# Brduino-Main.net
KiCad netlist of a schematic drawn in Altium Designer
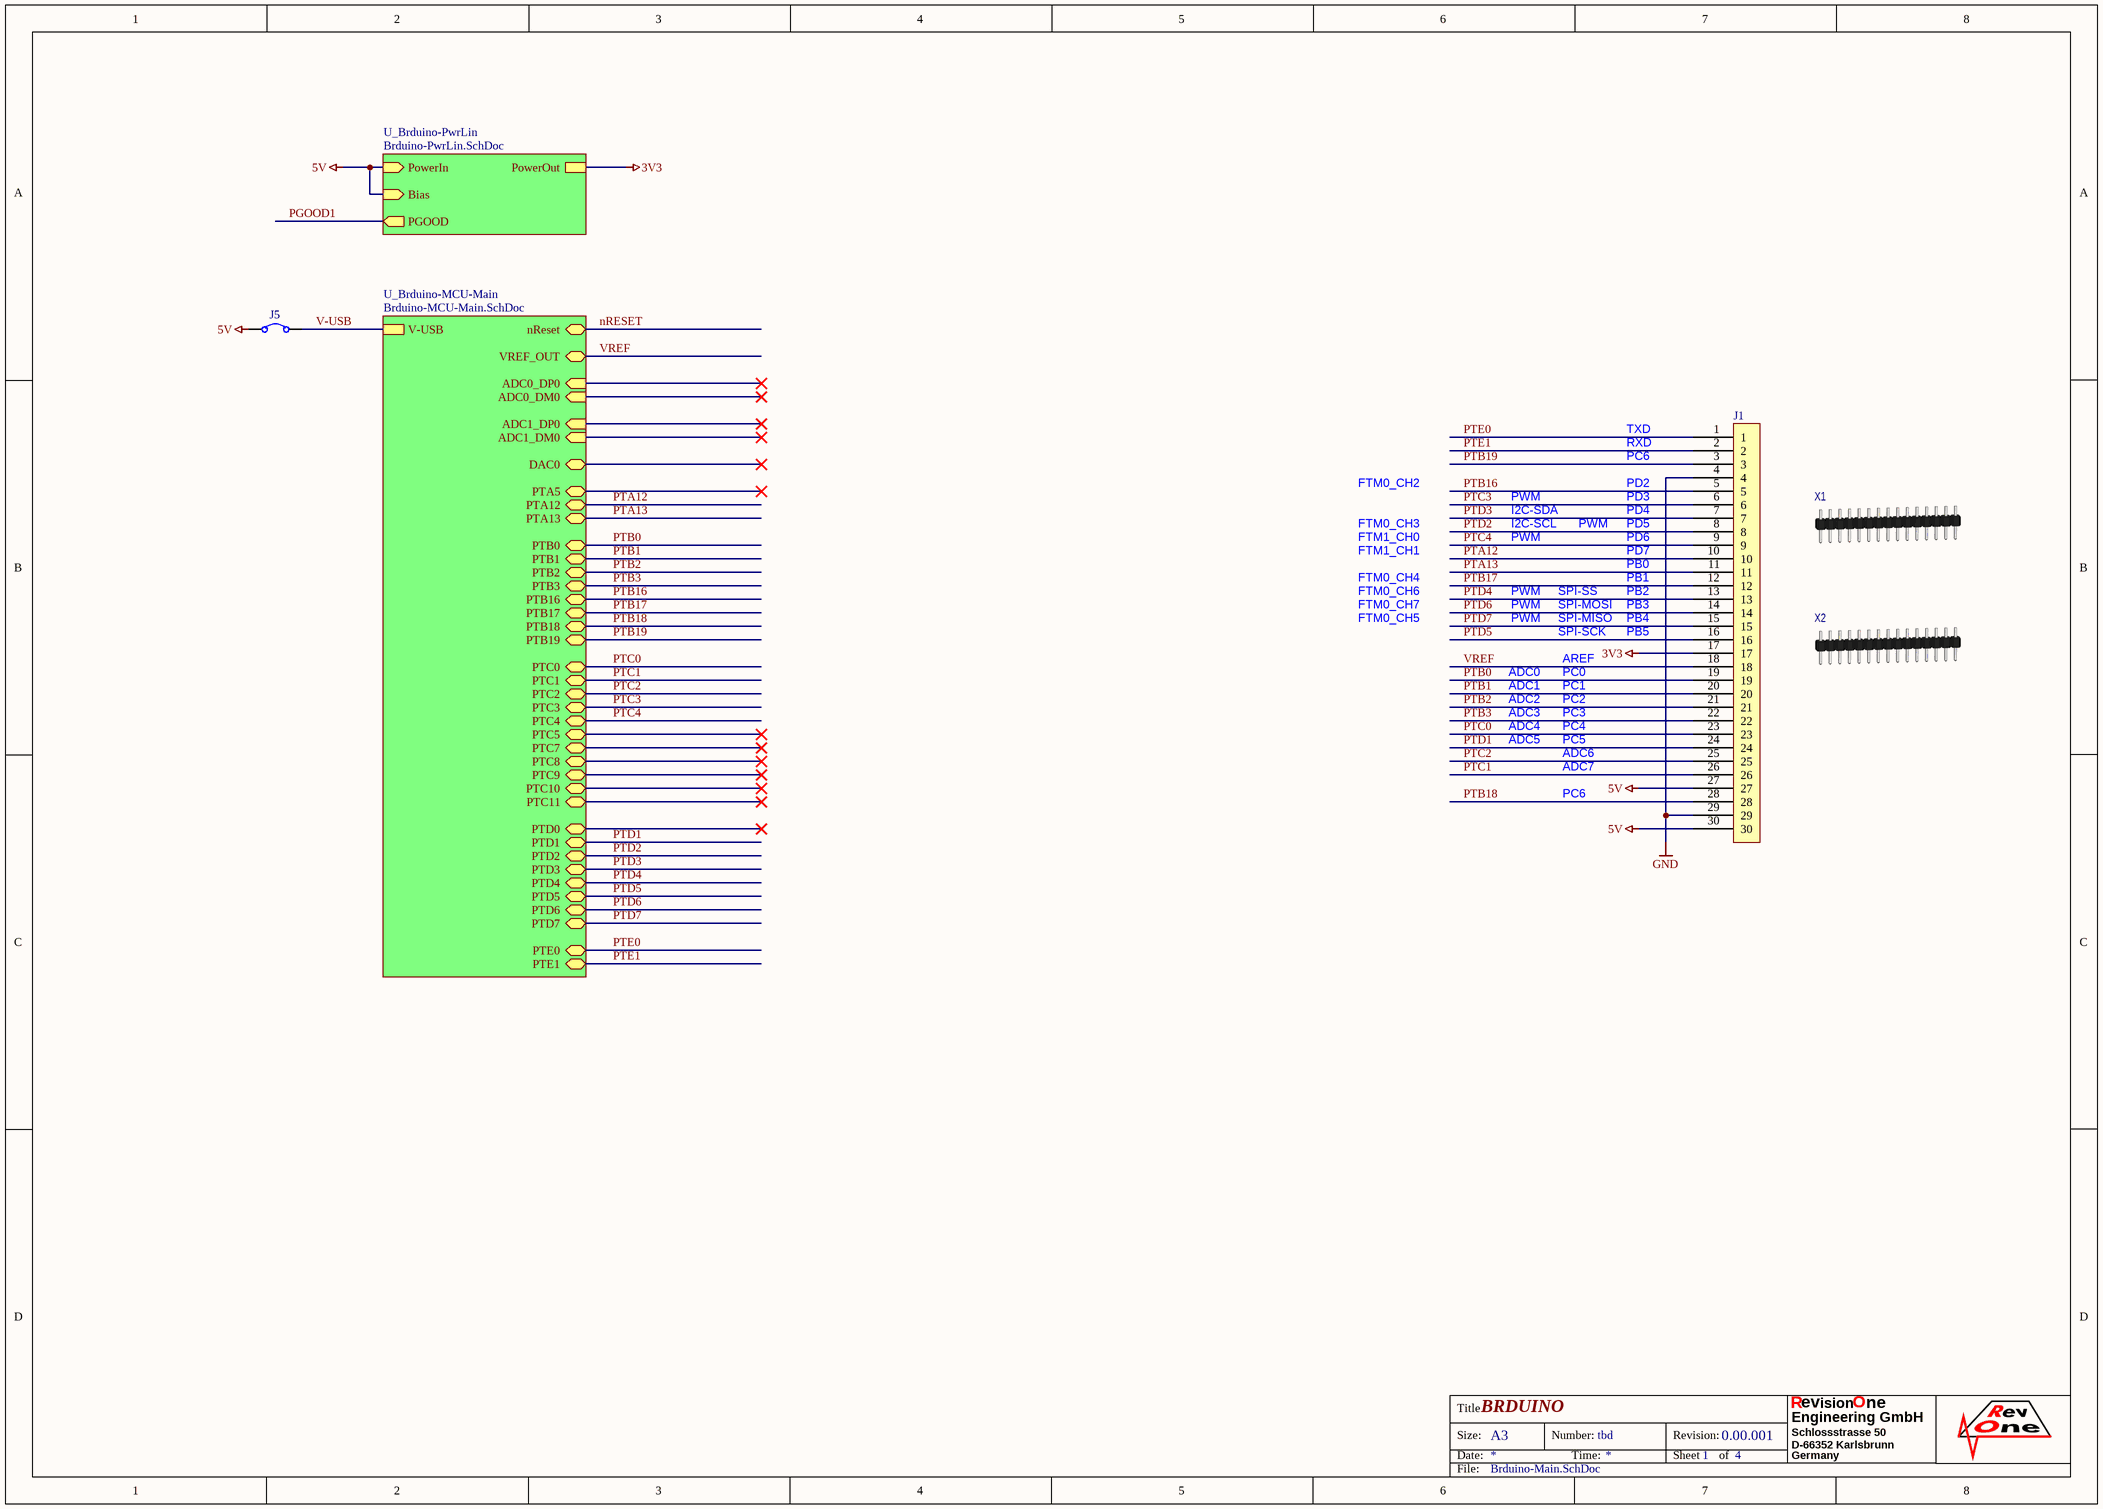
[diagram p0: Brduino-Main.SchDoc]

(export (version "E")
  (design (tool "Eeschema 10.0.6"))
  (components
    (comp (ref "J1")
      (value "X")
      (footprint "ARDUINO-NANO")
      (libsource (lib "Brduino-Nano") (part "ARDUINO-NANO-CON"))
    )
    (comp (ref "J5")
      (value "R")
      (footprint "JumperSMD")
      (description "RES SMD 0 OHM JUMPER 1/10W 0603")
      (libsource (lib "Brduino-Nano") (part "Jumper"))
    )
    (comp (ref "X1")
      (value "X")
      (description "CONN HEADER VERT 15POS 2.54MM")
      (libsource (lib "Brduino-Nano") (part "TSW-115-08-F-S"))
    )
    (comp (ref "X2")
      (value "X")
      (description "CONN HEADER VERT 15POS 2.54MM")
      (libsource (lib "Brduino-Nano") (part "TSW-115-08-F-S"))
    )
  )
  (nets
    (net (code "8") (name "/PTA12") (class "Default")
      (node (ref "J1") (pin "10") (pinfunction "10_10") (pintype "passive"))
    )
    (net (code "9") (name "/PTA13") (class "Default")
      (node (ref "J1") (pin "11") (pinfunction "11_11") (pintype "passive"))
    )
    (net (code "10") (name "/PTB0") (class "Default")
      (node (ref "J1") (pin "19") (pinfunction "19_19") (pintype "passive"))
    )
    (net (code "11") (name "/PTB1") (class "Default")
      (node (ref "J1") (pin "20") (pinfunction "20_20") (pintype "passive"))
    )
    (net (code "12") (name "/PTB2") (class "Default")
      (node (ref "J1") (pin "21") (pinfunction "21_21") (pintype "passive"))
    )
    (net (code "13") (name "/PTB3") (class "Default")
      (node (ref "J1") (pin "22") (pinfunction "22_22") (pintype "passive"))
    )
    (net (code "14") (name "/PTB16") (class "Default")
      (node (ref "J1") (pin "5") (pinfunction "5_5") (pintype "passive"))
    )
    (net (code "15") (name "/PTB17") (class "Default")
      (node (ref "J1") (pin "12") (pinfunction "12_12") (pintype "passive"))
    )
    (net (code "16") (name "/PTB18") (class "Default")
      (node (ref "J1") (pin "28") (pinfunction "28_28") (pintype "passive"))
    )
    (net (code "17") (name "/PTB19") (class "Default")
      (node (ref "J1") (pin "3") (pinfunction "3_3") (pintype "passive"))
    )
    (net (code "18") (name "/PTC0") (class "Default")
      (node (ref "J1") (pin "23") (pinfunction "23_23") (pintype "passive"))
    )
    (net (code "19") (name "/PTC1") (class "Default")
      (node (ref "J1") (pin "26") (pinfunction "26_26") (pintype "passive"))
    )
    (net (code "20") (name "/PTC2") (class "Default")
      (node (ref "J1") (pin "25") (pinfunction "25_25") (pintype "passive"))
    )
    (net (code "21") (name "/PTC3") (class "Default")
      (node (ref "J1") (pin "6") (pinfunction "6_6") (pintype "passive"))
    )
    (net (code "22") (name "/PTC4") (class "Default")
      (node (ref "J1") (pin "9") (pinfunction "9_9") (pintype "passive"))
    )
    (net (code "30") (name "/PTD1") (class "Default")
      (node (ref "J1") (pin "24") (pinfunction "24_24") (pintype "passive"))
    )
    (net (code "31") (name "/PTD2") (class "Default")
      (node (ref "J1") (pin "8") (pinfunction "8_8") (pintype "passive"))
    )
    (net (code "32") (name "/PTD3") (class "Default")
      (node (ref "J1") (pin "7") (pinfunction "7_7") (pintype "passive"))
    )
    (net (code "33") (name "/PTD4") (class "Default")
      (node (ref "J1") (pin "13") (pinfunction "13_13") (pintype "passive"))
    )
    (net (code "34") (name "/PTD5") (class "Default")
      (node (ref "J1") (pin "16") (pinfunction "16_16") (pintype "passive"))
    )
    (net (code "35") (name "/PTD6") (class "Default")
      (node (ref "J1") (pin "14") (pinfunction "14_14") (pintype "passive"))
    )
    (net (code "36") (name "/PTD7") (class "Default")
      (node (ref "J1") (pin "15") (pinfunction "15_15") (pintype "passive"))
    )
    (net (code "37") (name "/PTE0") (class "Default")
      (node (ref "J1") (pin "1") (pinfunction "1_1") (pintype "passive"))
    )
    (net (code "38") (name "/PTE1") (class "Default")
      (node (ref "J1") (pin "2") (pinfunction "2_2") (pintype "passive"))
    )
    (net (code "39") (name "/V-USB") (class "Default")
      (node (ref "J5") (pin "2") (pinfunction "2_2") (pintype "passive"))
    )
    (net (code "40") (name "/VREF") (class "Default")
      (node (ref "J1") (pin "18") (pinfunction "18_18") (pintype "passive"))
    )
    (net (code "42") (name "3V3") (class "Default")
      (node (ref "J1") (pin "17") (pinfunction "17_17") (pintype "passive"))
    )
    (net (code "43") (name "5V") (class "Default")
      (node (ref "J1") (pin "27") (pinfunction "27_27") (pintype "passive"))
      (node (ref "J1") (pin "30") (pinfunction "30_30") (pintype "passive"))
      (node (ref "J5") (pin "1") (pinfunction "1_1") (pintype "passive"))
    )
    (net (code "44") (name "GND") (class "Default")
      (node (ref "J1") (pin "29") (pinfunction "29_29") (pintype "passive"))
      (node (ref "J1") (pin "4") (pinfunction "4_4") (pintype "passive"))
    )
  )
)
